# Sensors.net
KiCad netlist of a schematic drawn in Altium Designer
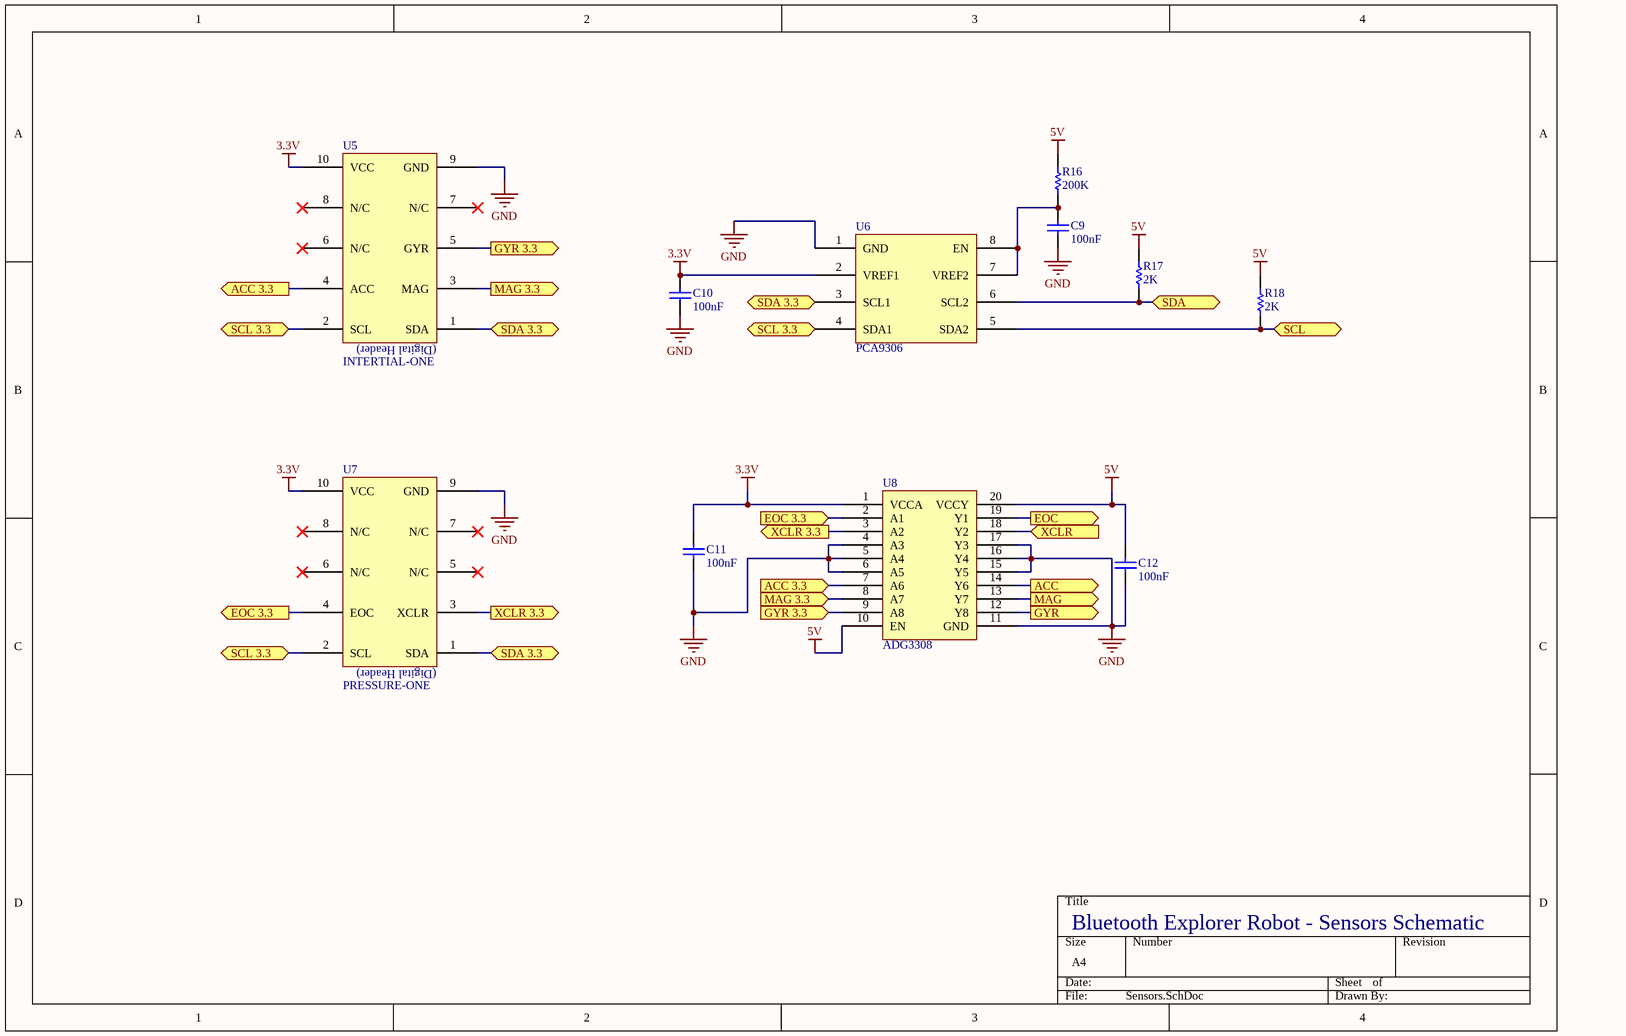
[diagram p0: Sensors.SchDoc]

(export (version "E")
  (design (tool "Eeschema 10.0.6"))
  (components
    (comp (ref "C9")
      (value "100nF")
      (footprint "KEMET Chip Capacitor:0805")
      (description "Capacitor (Semiconductor SIM Model)")
      (fields (field (name "PUBLISHER") "Altium Limited"))
      (libsource (lib "Miscellaneous Devices") (part "Cap Semi"))
    )
    (comp (ref "C10")
      (value "100nF")
      (footprint "KEMET Chip Capacitor:0805")
      (description "Capacitor (Semiconductor SIM Model)")
      (fields (field (name "PUBLISHER") "Altium Limited"))
      (libsource (lib "Miscellaneous Devices") (part "Cap Semi"))
    )
    (comp (ref "C11")
      (value "100nF")
      (footprint "KEMET Chip Capacitor:0805")
      (description "Capacitor (Semiconductor SIM Model)")
      (fields (field (name "PUBLISHER") "Altium Limited"))
      (libsource (lib "Miscellaneous Devices") (part "Cap Semi"))
    )
    (comp (ref "C12")
      (value "100nF")
      (footprint "KEMET Chip Capacitor:0805")
      (description "Capacitor (Semiconductor SIM Model)")
      (fields (field (name "PUBLISHER") "Altium Limited"))
      (libsource (lib "Miscellaneous Devices") (part "Cap Semi"))
    )
    (comp (ref "R16")
      (value "200K")
      (footprint "2012[0805]")
      (description "Semiconductor Resistor")
      (fields (field (name "Comment") "Res Semi") (field (name "PUBLISHER") "Altium Limited"))
      (libsource (lib "Miscellaneous Devices") (part "Res Semi"))
    )
    (comp (ref "R17")
      (value "2K")
      (footprint "2012[0805]")
      (description "Semiconductor Resistor")
      (fields (field (name "Comment") "Res Semi") (field (name "PUBLISHER") "Altium Limited"))
      (libsource (lib "Miscellaneous Devices") (part "Res Semi"))
    )
    (comp (ref "R18")
      (value "2K")
      (footprint "2012[0805]")
      (description "Semiconductor Resistor")
      (fields (field (name "Comment") "Res Semi") (field (name "PUBLISHER") "Altium Limited"))
      (libsource (lib "Miscellaneous Devices") (part "Res Semi"))
    )
    (comp (ref "U5")
      (value "INTERTIAL-ONE")
      (footprint "ATMEL-SENS")
      (libsource (lib "AtmelSensorBoards") (part "INTERTIAL-ONE"))
    )
    (comp (ref "U6") (value "PCA9306") (footprint "us8") (libsource (lib "MiscParts") (part "PCA9306")))
    (comp (ref "U7")
      (value "PRESSURE-ONE")
      (footprint "ATMEL-SENS")
      (libsource (lib "AtmelSensorBoards") (part "PRESSURE-ONE"))
    )
    (comp (ref "U8") (value "ADG3308") (footprint "TSSOP20") (libsource (lib "MiscParts") (part "ADG3308")))
  )
  (nets
    (net (code "1") (name "/ACC") (class "Default")
      (node (ref "U8") (pin "14") (pinfunction "Y6_14") (pintype "passive"))
    )
    (net (code "2") (name "/ACC 3.3") (class "Default")
      (node (ref "U5") (pin "4") (pinfunction "ACC_4") (pintype "passive"))
      (node (ref "U8") (pin "7") (pinfunction "A6_7") (pintype "passive"))
    )
    (net (code "3") (name "/EOC") (class "Default")
      (node (ref "U8") (pin "19") (pinfunction "Y1_19") (pintype "passive"))
    )
    (net (code "4") (name "/EOC 3.3") (class "Default")
      (node (ref "U7") (pin "4") (pinfunction "EOC_4") (pintype "passive"))
      (node (ref "U8") (pin "2") (pinfunction "A1_2") (pintype "passive"))
    )
    (net (code "5") (name "/GYR") (class "Default")
      (node (ref "U8") (pin "12") (pinfunction "Y8_12") (pintype "passive"))
    )
    (net (code "6") (name "/GYR 3.3") (class "Default")
      (node (ref "U5") (pin "5") (pinfunction "GYR_5") (pintype "passive"))
      (node (ref "U8") (pin "9") (pinfunction "A8_9") (pintype "passive"))
    )
    (net (code "7") (name "/MAG") (class "Default")
      (node (ref "U8") (pin "13") (pinfunction "Y7_13") (pintype "passive"))
    )
    (net (code "8") (name "/MAG 3.3") (class "Default")
      (node (ref "U5") (pin "3") (pinfunction "MAG_3") (pintype "passive"))
      (node (ref "U8") (pin "8") (pinfunction "A7_8") (pintype "passive"))
    )
    (net (code "9") (name "/SCL") (class "Default")
      (node (ref "R18") (pin "1") (pinfunction "1_1") (pintype "passive"))
      (node (ref "U6") (pin "5") (pinfunction "SDA2_5") (pintype "passive"))
    )
    (net (code "10") (name "/SCL 3.3") (class "Default")
      (node (ref "U5") (pin "2") (pinfunction "SCL_2") (pintype "passive"))
      (node (ref "U6") (pin "4") (pinfunction "SDA1_4") (pintype "passive"))
      (node (ref "U7") (pin "2") (pinfunction "SCL_2") (pintype "passive"))
    )
    (net (code "11") (name "/SDA") (class "Default")
      (node (ref "R17") (pin "1") (pinfunction "1_1") (pintype "passive"))
      (node (ref "U6") (pin "6") (pinfunction "SCL2_6") (pintype "passive"))
    )
    (net (code "12") (name "/SDA 3.3") (class "Default")
      (node (ref "U5") (pin "1") (pinfunction "SDA_1") (pintype "passive"))
      (node (ref "U6") (pin "3") (pinfunction "SCL1_3") (pintype "passive"))
      (node (ref "U7") (pin "1") (pinfunction "SDA_1") (pintype "passive"))
    )
    (net (code "13") (name "/XCLR") (class "Default")
      (node (ref "U8") (pin "18") (pinfunction "Y2_18") (pintype "passive"))
    )
    (net (code "14") (name "/XCLR 3.3") (class "Default")
      (node (ref "U7") (pin "3") (pinfunction "XCLR_3") (pintype "passive"))
      (node (ref "U8") (pin "3") (pinfunction "A2_3") (pintype "passive"))
    )
    (net (code "15") (name "3.3V") (class "Default")
      (node (ref "C10") (pin "1") (pinfunction "1_1") (pintype "passive"))
      (node (ref "C11") (pin "1") (pinfunction "1_1") (pintype "passive"))
      (node (ref "U5") (pin "10") (pinfunction "VCC_10") (pintype "passive"))
      (node (ref "U6") (pin "2") (pinfunction "VREF1_2") (pintype "passive"))
      (node (ref "U7") (pin "10") (pinfunction "VCC_10") (pintype "passive"))
      (node (ref "U8") (pin "1") (pinfunction "VCCA_1") (pintype "passive"))
    )
    (net (code "16") (name "5V") (class "Default")
      (node (ref "C12") (pin "1") (pinfunction "1_1") (pintype "passive"))
      (node (ref "R16") (pin "2") (pinfunction "2_2") (pintype "passive"))
      (node (ref "R17") (pin "2") (pinfunction "2_2") (pintype "passive"))
      (node (ref "R18") (pin "2") (pinfunction "2_2") (pintype "passive"))
      (node (ref "U8") (pin "10") (pinfunction "EN_10") (pintype "passive"))
      (node (ref "U8") (pin "20") (pinfunction "VCCY_20") (pintype "passive"))
    )
    (net (code "17") (name "GND") (class "Default")
      (node (ref "C10") (pin "2") (pinfunction "2_2") (pintype "passive"))
      (node (ref "C11") (pin "2") (pinfunction "2_2") (pintype "passive"))
      (node (ref "C12") (pin "2") (pinfunction "2_2") (pintype "passive"))
      (node (ref "C9") (pin "2") (pinfunction "2_2") (pintype "passive"))
      (node (ref "U5") (pin "9") (pinfunction "GND_9") (pintype "passive"))
      (node (ref "U6") (pin "1") (pinfunction "GND_1") (pintype "passive"))
      (node (ref "U7") (pin "9") (pinfunction "GND_9") (pintype "passive"))
      (node (ref "U8") (pin "11") (pinfunction "GND_11") (pintype "passive"))
      (node (ref "U8") (pin "15") (pinfunction "Y5_15") (pintype "passive"))
      (node (ref "U8") (pin "16") (pinfunction "Y4_16") (pintype "passive"))
      (node (ref "U8") (pin "17") (pinfunction "Y3_17") (pintype "passive"))
      (node (ref "U8") (pin "4") (pinfunction "A3_4") (pintype "passive"))
      (node (ref "U8") (pin "5") (pinfunction "A4_5") (pintype "passive"))
      (node (ref "U8") (pin "6") (pinfunction "A5_6") (pintype "passive"))
    )
    (net (code "18") (name "Net-(U6-EN)") (class "Default")
      (node (ref "C9") (pin "1") (pinfunction "1_1") (pintype "passive"))
      (node (ref "R16") (pin "1") (pinfunction "1_1") (pintype "passive"))
      (node (ref "U6") (pin "7") (pinfunction "VREF2_7") (pintype "passive"))
      (node (ref "U6") (pin "8") (pinfunction "EN_8") (pintype "passive"))
    )
    (net (code "19") (name "unconnected-(U5-N{slash}C-Pad6)") (class "Default")
      (node (ref "U5") (pin "6") (pinfunction "N/C_6") (pintype "passive+no_connect"))
    )
    (net (code "20") (name "unconnected-(U5-N{slash}C-Pad7)") (class "Default")
      (node (ref "U5") (pin "7") (pinfunction "N/C_7") (pintype "passive+no_connect"))
    )
    (net (code "21") (name "unconnected-(U5-N{slash}C-Pad8)") (class "Default")
      (node (ref "U5") (pin "8") (pinfunction "N/C_8") (pintype "passive+no_connect"))
    )
    (net (code "22") (name "unconnected-(U7-N{slash}C-Pad5)") (class "Default")
      (node (ref "U7") (pin "5") (pinfunction "N/C_5") (pintype "passive+no_connect"))
    )
    (net (code "23") (name "unconnected-(U7-N{slash}C-Pad6)") (class "Default")
      (node (ref "U7") (pin "6") (pinfunction "N/C_6") (pintype "passive+no_connect"))
    )
    (net (code "24") (name "unconnected-(U7-N{slash}C-Pad7)") (class "Default")
      (node (ref "U7") (pin "7") (pinfunction "N/C_7") (pintype "passive+no_connect"))
    )
    (net (code "25") (name "unconnected-(U7-N{slash}C-Pad8)") (class "Default")
      (node (ref "U7") (pin "8") (pinfunction "N/C_8") (pintype "passive+no_connect"))
    )
  )
)
